# Adafruit_Si1145_Breakout.net
KiCad netlist of a schematic drawn in EAGLE
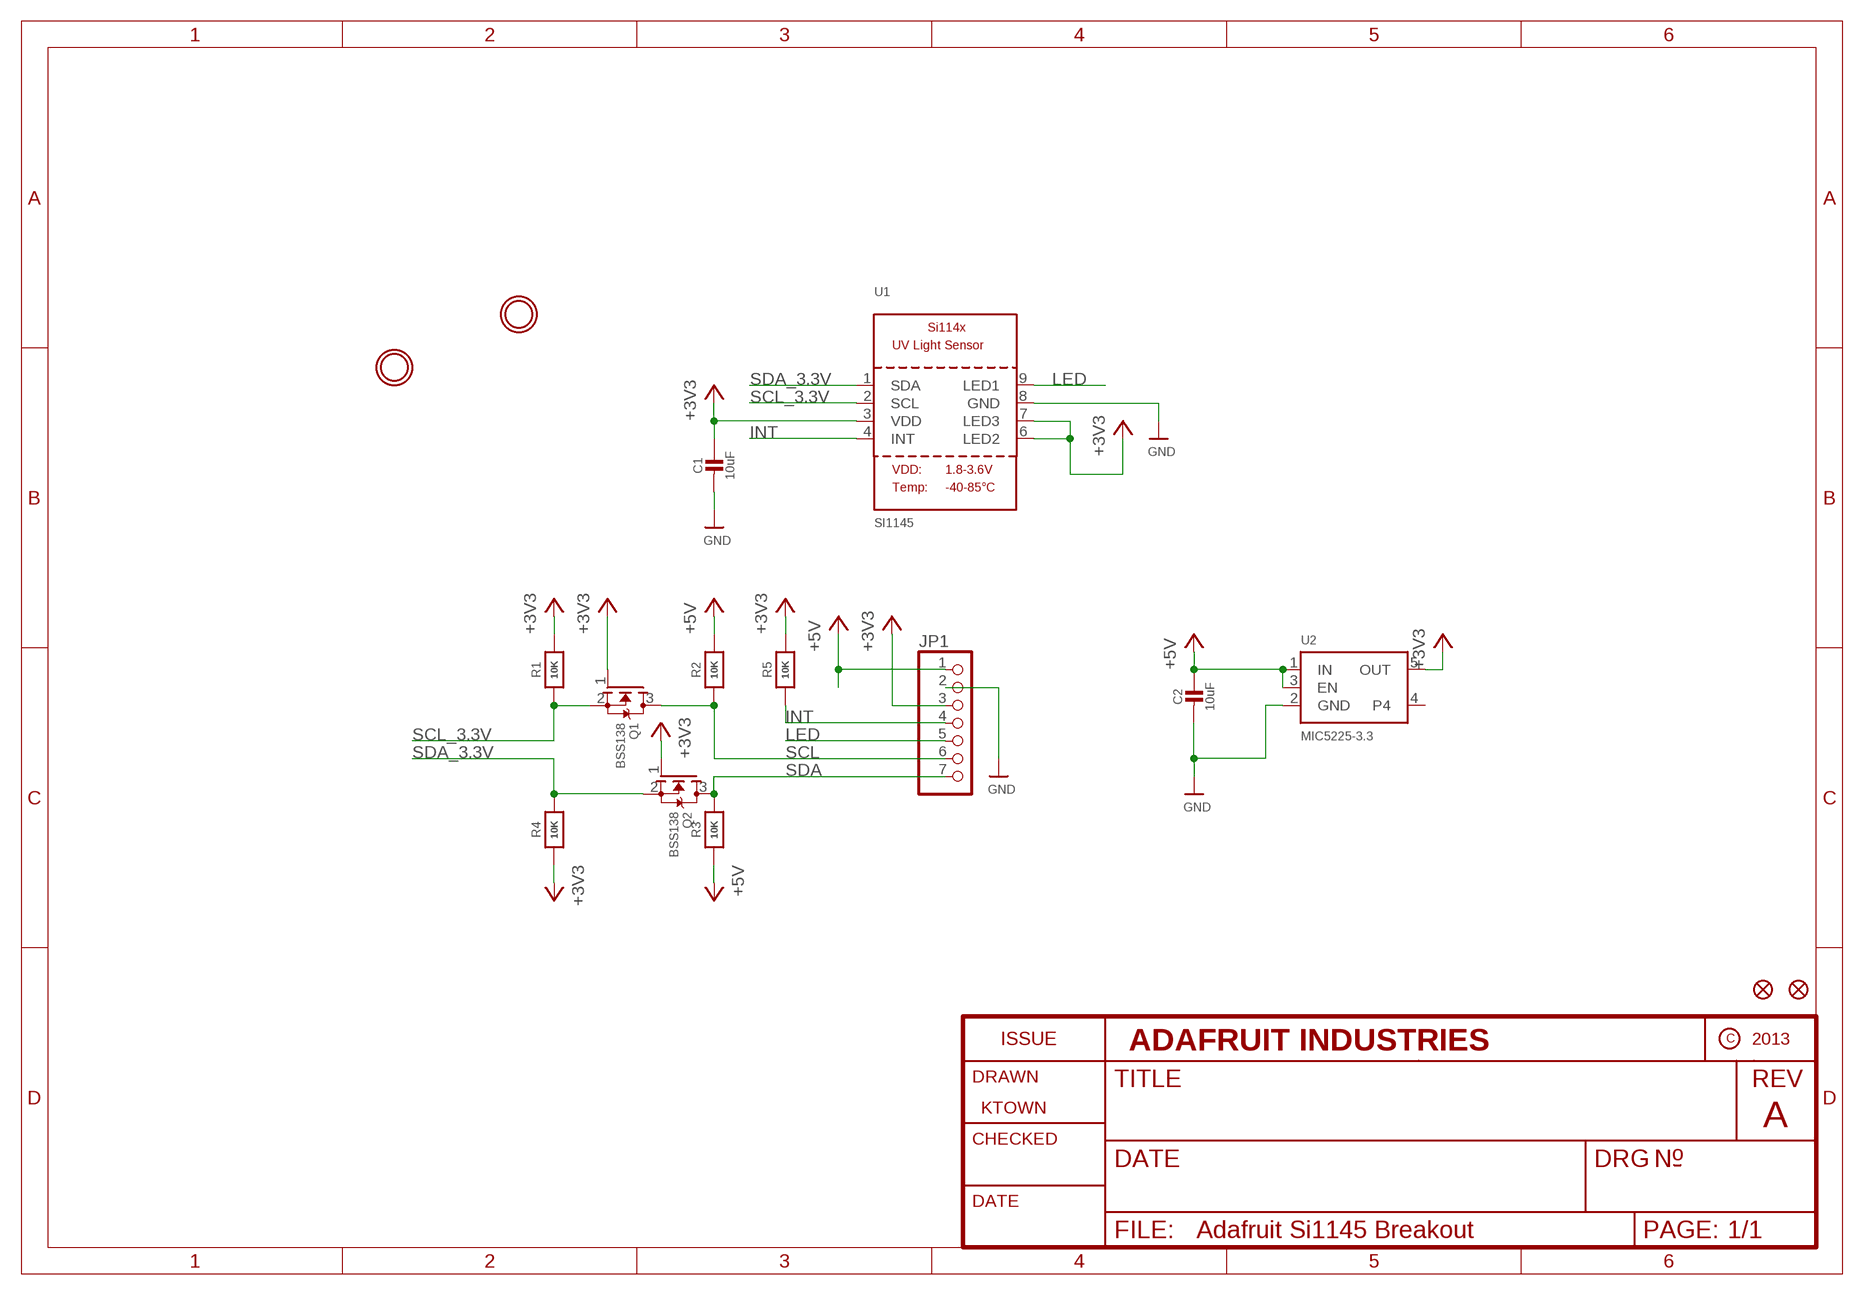
[diagram p0: schematic, sheet 1]

(export (version "E")
  (design (tool "Eeschema 10.0.6"))
  (components
    (comp (ref "C1")
      (value "10uF")
      (footprint "eagle-import:0805-NO")
      (libsource (lib "eagle-import") (part "CAP_CERAMIC0805-NOOUTLINE"))
    )
    (comp (ref "C2")
      (value "10uF")
      (footprint "eagle-import:0805-NO")
      (libsource (lib "eagle-import") (part "CAP_CERAMIC0805-NOOUTLINE"))
    )
    (comp (ref "FID1")
      (value "FIDUCIAL\"\"")
      (footprint "eagle-import:FIDUCIAL_1MM")
      (libsource (lib "eagle-import") (part "FIDUCIAL{dblquote}{dblquote}"))
    )
    (comp (ref "FID2")
      (value "FIDUCIAL\"\"")
      (footprint "eagle-import:FIDUCIAL_1MM")
      (libsource (lib "eagle-import") (part "FIDUCIAL{dblquote}{dblquote}"))
    )
    (comp (ref "JP1")
      (value "HEADER-1X770MIL")
      (footprint "eagle-import:1X07_ROUND_70")
      (libsource (lib "eagle-import") (part "HEADER-1X770MIL"))
    )
    (comp (ref "Q1")
      (value "BSS138")
      (footprint "eagle-import:SOT23-WIDE")
      (libsource (lib "eagle-import") (part "MOSFET-NWIDE"))
    )
    (comp (ref "Q2")
      (value "BSS138")
      (footprint "eagle-import:SOT23-WIDE")
      (libsource (lib "eagle-import") (part "MOSFET-NWIDE"))
    )
    (comp (ref "R1")
      (value "10K")
      (footprint "eagle-import:0805-NO")
      (libsource (lib "eagle-import") (part "RESISTOR0805_NOOUTLINE"))
    )
    (comp (ref "R2")
      (value "10K")
      (footprint "eagle-import:0805-NO")
      (libsource (lib "eagle-import") (part "RESISTOR0805_NOOUTLINE"))
    )
    (comp (ref "R3")
      (value "10K")
      (footprint "eagle-import:0805-NO")
      (libsource (lib "eagle-import") (part "RESISTOR0805_NOOUTLINE"))
    )
    (comp (ref "R4")
      (value "10K")
      (footprint "eagle-import:0805-NO")
      (libsource (lib "eagle-import") (part "RESISTOR0805_NOOUTLINE"))
    )
    (comp (ref "R5")
      (value "10K")
      (footprint "eagle-import:0805-NO")
      (libsource (lib "eagle-import") (part "RESISTOR0805_NOOUTLINE"))
    )
    (comp (ref "U$5")
      (value "MOUNTINGHOLE2.5")
      (footprint "eagle-import:MOUNTINGHOLE_2.5_PLATED")
      (libsource (lib "eagle-import") (part "MOUNTINGHOLE2.5"))
    )
    (comp (ref "U$6")
      (value "MOUNTINGHOLE2.5")
      (footprint "eagle-import:MOUNTINGHOLE_2.5_PLATED")
      (libsource (lib "eagle-import") (part "MOUNTINGHOLE2.5"))
    )
    (comp (ref "U1")
      (value "SI1145")
      (footprint "eagle-import:SI114X")
      (libsource (lib "eagle-import") (part "SI114X"))
    )
    (comp (ref "U2")
      (value "MIC5225-3.3")
      (footprint "eagle-import:SOT23-5")
      (libsource (lib "eagle-import") (part "VREG_SOT23-5"))
    )
  )
  (nets
    (net (code "1") (name "+3V3") (class "Default")
      (node (ref "C1") (pin "1") (pinfunction "1_1") (pintype "passive"))
      (node (ref "JP1") (pin "3") (pinfunction "3_3") (pintype "passive"))
      (node (ref "Q1") (pin "1") (pinfunction "G_1") (pintype "bidirectional"))
      (node (ref "Q2") (pin "1") (pinfunction "G_1") (pintype "bidirectional"))
      (node (ref "R1") (pin "2") (pinfunction "2_2") (pintype "passive"))
      (node (ref "R4") (pin "1") (pinfunction "1_1") (pintype "passive"))
      (node (ref "R5") (pin "2") (pinfunction "2_2") (pintype "passive"))
      (node (ref "U1") (pin "3") (pinfunction "VDD_3") (pintype "power_in"))
      (node (ref "U1") (pin "6") (pinfunction "LED2_6") (pintype "open_collector"))
      (node (ref "U1") (pin "7") (pinfunction "LED3_7") (pintype "open_collector"))
      (node (ref "U2") (pin "5") (pinfunction "OUT_5") (pintype "power_in"))
    )
    (net (code "2") (name "+5V") (class "Default")
      (node (ref "C2") (pin "1") (pinfunction "1_1") (pintype "passive"))
      (node (ref "JP1") (pin "1") (pinfunction "1_1") (pintype "passive"))
      (node (ref "R2") (pin "2") (pinfunction "2_2") (pintype "passive"))
      (node (ref "R3") (pin "1") (pinfunction "1_1") (pintype "passive"))
      (node (ref "U2") (pin "1") (pinfunction "IN_1") (pintype "power_in"))
      (node (ref "U2") (pin "3") (pinfunction "EN_3") (pintype "input"))
    )
    (net (code "3") (name "/INT") (class "Default")
      (node (ref "JP1") (pin "4") (pinfunction "4_4") (pintype "passive"))
      (node (ref "R5") (pin "1") (pinfunction "1_1") (pintype "passive"))
      (node (ref "U1") (pin "4") (pinfunction "INT_4") (pintype "open_collector"))
    )
    (net (code "4") (name "/LED") (class "Default")
      (node (ref "JP1") (pin "5") (pinfunction "5_5") (pintype "passive"))
      (node (ref "U1") (pin "9") (pinfunction "LED1_9") (pintype "open_collector"))
    )
    (net (code "5") (name "/SCL") (class "Default")
      (node (ref "JP1") (pin "6") (pinfunction "6_6") (pintype "passive"))
      (node (ref "Q1") (pin "3") (pinfunction "D_3") (pintype "bidirectional"))
      (node (ref "R2") (pin "1") (pinfunction "1_1") (pintype "passive"))
    )
    (net (code "6") (name "/SCL_3.3V") (class "Default")
      (node (ref "Q1") (pin "2") (pinfunction "S_2") (pintype "bidirectional"))
      (node (ref "R1") (pin "1") (pinfunction "1_1") (pintype "passive"))
      (node (ref "U1") (pin "2") (pinfunction "SCL_2") (pintype "input"))
    )
    (net (code "7") (name "/SDA") (class "Default")
      (node (ref "JP1") (pin "7") (pinfunction "7_7") (pintype "passive"))
      (node (ref "Q2") (pin "3") (pinfunction "D_3") (pintype "bidirectional"))
      (node (ref "R3") (pin "2") (pinfunction "2_2") (pintype "passive"))
    )
    (net (code "8") (name "/SDA_3.3V") (class "Default")
      (node (ref "Q2") (pin "2") (pinfunction "S_2") (pintype "bidirectional"))
      (node (ref "R4") (pin "2") (pinfunction "2_2") (pintype "passive"))
      (node (ref "U1") (pin "1") (pinfunction "SDA_1") (pintype "bidirectional"))
    )
    (net (code "9") (name "GND") (class "Default")
      (node (ref "C1") (pin "2") (pinfunction "2_2") (pintype "passive"))
      (node (ref "C2") (pin "2") (pinfunction "2_2") (pintype "passive"))
      (node (ref "JP1") (pin "2") (pinfunction "2_2") (pintype "passive"))
      (node (ref "U1") (pin "8") (pinfunction "GND_8") (pintype "power_in"))
      (node (ref "U2") (pin "2") (pinfunction "GND_2") (pintype "power_in"))
    )
    (net (code "10") (name "unconnected-(U2-P4-Pad4)") (class "Default")
      (node (ref "U2") (pin "4") (pinfunction "P4_4") (pintype "bidirectional"))
    )
  )
)
